# Autoreset.net
KiCad netlist of a schematic drawn in Altium Designer
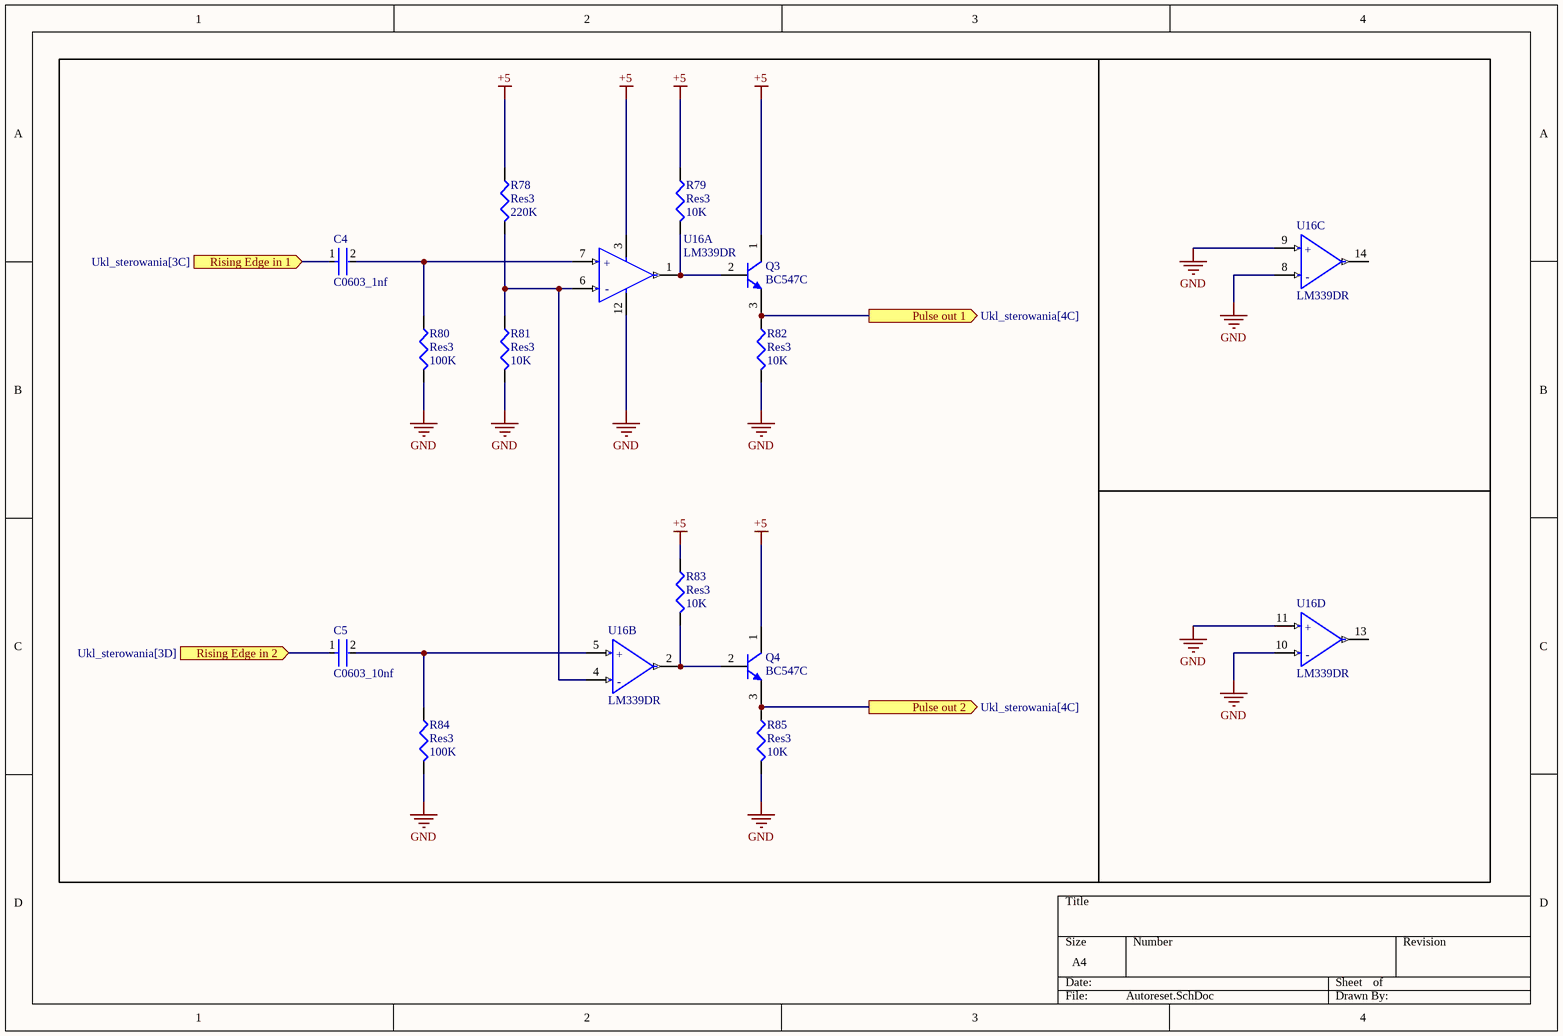
[diagram p0: Autoreset.SchDoc]

(export (version "E")
  (design (tool "Eeschema 10.0.6"))
  (components
    (comp (ref "C4")
      (value "C0603_1nf")
      (footprint "FP-C0603C-CF-MFG")
      (description "CAP CER 30PF 50V 5% NP0 0603")
      (fields
        (field (name "MANUFACTURER PART NUMBER") "C0603C300J5GACTU")
        (field (name "MANUFACTURER") "KEMET")
      )
      (libsource (lib "Altium Content Vault") (part "b4654b650e69147ec39a6b967a45e02"))
    )
    (comp (ref "C5")
      (value "C0603_10nf")
      (footprint "FP-C0603C-CF-MFG")
      (description "CAP CER 30PF 50V 5% NP0 0603")
      (fields
        (field (name "MANUFACTURER PART NUMBER") "C0603C300J5GACTU")
        (field (name "MANUFACTURER") "KEMET")
      )
      (libsource (lib "Altium Content Vault") (part "b4654b650e69147ec39a6b967a45e02"))
    )
    (comp (ref "Q3")
      (value "BC547C")
      (footprint "ONSC-TO-92-3-29-11")
      (description "Amplifier Transistor, NPN Silicon, 3-Pin TO-92, Bulk Box")
      (fields (field (name "MANUFACTURER") "On Semiconductor"))
      (libsource (lib "Altium Content Vault") (part "ONSC-NPN-C1B2E3-3"))
    )
    (comp (ref "Q4")
      (value "BC547C")
      (footprint "ONSC-TO-92-3-29-11")
      (description "Amplifier Transistor, NPN Silicon, 3-Pin TO-92, Bulk Box")
      (fields (field (name "MANUFACTURER") "On Semiconductor"))
      (libsource (lib "Altium Content Vault") (part "ONSC-NPN-C1B2E3-3"))
    )
    (comp (ref "R78")
      (value "Res3")
      (footprint "J1-0603")
      (description "Resistor")
      (fields (field (name "ALTIUM_VALUE") "220K") (field (name "PUBLISHER") "Altium Limited"))
      (libsource (lib "Miscellaneous Devices") (part "Res3"))
    )
    (comp (ref "R79")
      (value "Res3")
      (footprint "J1-0603")
      (description "Resistor")
      (fields (field (name "ALTIUM_VALUE") "10K") (field (name "PUBLISHER") "Altium Limited"))
      (libsource (lib "Miscellaneous Devices") (part "Res3"))
    )
    (comp (ref "R80")
      (value "Res3")
      (footprint "J1-0603")
      (description "Resistor")
      (fields (field (name "ALTIUM_VALUE") "100K") (field (name "PUBLISHER") "Altium Limited"))
      (libsource (lib "Miscellaneous Devices") (part "Res3"))
    )
    (comp (ref "R81")
      (value "Res3")
      (footprint "J1-0603")
      (description "Resistor")
      (fields (field (name "ALTIUM_VALUE") "10K") (field (name "PUBLISHER") "Altium Limited"))
      (libsource (lib "Miscellaneous Devices") (part "Res3"))
    )
    (comp (ref "R82")
      (value "Res3")
      (footprint "J1-0603")
      (description "Resistor")
      (fields (field (name "ALTIUM_VALUE") "10K") (field (name "PUBLISHER") "Altium Limited"))
      (libsource (lib "Miscellaneous Devices") (part "Res3"))
    )
    (comp (ref "R83")
      (value "Res3")
      (footprint "J1-0603")
      (description "Resistor")
      (fields (field (name "ALTIUM_VALUE") "10K") (field (name "PUBLISHER") "Altium Limited"))
      (libsource (lib "Miscellaneous Devices") (part "Res3"))
    )
    (comp (ref "R84")
      (value "Res3")
      (footprint "J1-0603")
      (description "Resistor")
      (fields (field (name "ALTIUM_VALUE") "100K") (field (name "PUBLISHER") "Altium Limited"))
      (libsource (lib "Miscellaneous Devices") (part "Res3"))
    )
    (comp (ref "R85")
      (value "Res3")
      (footprint "J1-0603")
      (description "Resistor")
      (fields (field (name "ALTIUM_VALUE") "10K") (field (name "PUBLISHER") "Altium Limited"))
      (libsource (lib "Miscellaneous Devices") (part "Res3"))
    )
    (comp (ref "U16")
      (value "LM339DR")
      (footprint "FP-D0014A-MFG")
      (description "IC QUAD DIFF COMP 14-SOIC")
      (fields
        (field (name "OCTOPART") "https://octopart.com/lm339dr-texas+instruments-45532")
        (field (name "MANUFACTURER") "Texas Instruments")
      )
      (libsource (lib "Altium Content Vault") (part "e40d3f79f05c88e03941af0c3538ad1"))
    )
  )
  (nets
    (net (code "1") (name "+5") (class "Default")
      (node (ref "Q3") (pin "1") (pinfunction "C_1") (pintype "passive"))
      (node (ref "Q4") (pin "1") (pinfunction "C_1") (pintype "passive"))
      (node (ref "R78") (pin "1") (pinfunction "1_1") (pintype "passive"))
      (node (ref "R79") (pin "1") (pinfunction "1_1") (pintype "passive"))
      (node (ref "R83") (pin "1") (pinfunction "1_1") (pintype "passive"))
      (node (ref "U16") (pin "3") (pinfunction "VCC_3") (pintype "power_in"))
    )
    (net (code "2") (name "/Pulse out 1") (class "Default")
      (node (ref "Q3") (pin "3") (pinfunction "E_3") (pintype "passive"))
      (node (ref "R82") (pin "1") (pinfunction "1_1") (pintype "passive"))
    )
    (net (code "3") (name "/Pulse out 2") (class "Default")
      (node (ref "Q4") (pin "3") (pinfunction "E_3") (pintype "passive"))
      (node (ref "R85") (pin "1") (pinfunction "1_1") (pintype "passive"))
    )
    (net (code "4") (name "/Rising Edge in 1") (class "Default")
      (node (ref "C4") (pin "1") (pinfunction "1_1") (pintype "passive"))
    )
    (net (code "5") (name "/Rising Edge in 2") (class "Default")
      (node (ref "C5") (pin "1") (pinfunction "1_1") (pintype "passive"))
    )
    (net (code "6") (name "GND") (class "Default")
      (node (ref "R80") (pin "2") (pinfunction "2_2") (pintype "passive"))
      (node (ref "R81") (pin "2") (pinfunction "2_2") (pintype "passive"))
      (node (ref "R82") (pin "2") (pinfunction "2_2") (pintype "passive"))
      (node (ref "R84") (pin "2") (pinfunction "2_2") (pintype "passive"))
      (node (ref "R85") (pin "2") (pinfunction "2_2") (pintype "passive"))
      (node (ref "U16") (pin "10") (pinfunction "4IN-_10") (pintype "input"))
      (node (ref "U16") (pin "11") (pinfunction "4IN+_11") (pintype "input"))
      (node (ref "U16") (pin "12") (pinfunction "GND_12") (pintype "power_in"))
      (node (ref "U16") (pin "8") (pinfunction "3IN-_8") (pintype "input"))
      (node (ref "U16") (pin "9") (pinfunction "3IN+_9") (pintype "input"))
    )
    (net (code "7") (name "Net-(Q3-B)") (class "Default")
      (node (ref "Q3") (pin "2") (pinfunction "B_2") (pintype "passive"))
      (node (ref "R79") (pin "2") (pinfunction "2_2") (pintype "passive"))
      (node (ref "U16") (pin "1") (pinfunction "1OUT_1") (pintype "output"))
    )
    (net (code "8") (name "Net-(Q4-B)") (class "Default")
      (node (ref "Q4") (pin "2") (pinfunction "B_2") (pintype "passive"))
      (node (ref "R83") (pin "2") (pinfunction "2_2") (pintype "passive"))
      (node (ref "U16") (pin "2") (pinfunction "2OUT_2") (pintype "output"))
    )
    (net (code "9") (name "Net-(U16A-1IN+)") (class "Default")
      (node (ref "C4") (pin "2") (pinfunction "2_2") (pintype "passive"))
      (node (ref "R80") (pin "1") (pinfunction "1_1") (pintype "passive"))
      (node (ref "U16") (pin "7") (pinfunction "1IN+_7") (pintype "input"))
    )
    (net (code "10") (name "Net-(U16A-1IN-)") (class "Default")
      (node (ref "R78") (pin "2") (pinfunction "2_2") (pintype "passive"))
      (node (ref "R81") (pin "1") (pinfunction "1_1") (pintype "passive"))
      (node (ref "U16") (pin "4") (pinfunction "2IN-_4") (pintype "input"))
      (node (ref "U16") (pin "6") (pinfunction "1IN-_6") (pintype "input"))
    )
    (net (code "11") (name "Net-(U16B-2IN+)") (class "Default")
      (node (ref "C5") (pin "2") (pinfunction "2_2") (pintype "passive"))
      (node (ref "R84") (pin "1") (pinfunction "1_1") (pintype "passive"))
      (node (ref "U16") (pin "5") (pinfunction "2IN+_5") (pintype "input"))
    )
    (net (code "12") (name "unconnected-(U16C-OUT3-Pad14)") (class "Default")
      (node (ref "U16") (pin "14") (pinfunction "OUT3_14") (pintype "output"))
    )
    (net (code "13") (name "unconnected-(U16D-OUT4-Pad13)") (class "Default")
      (node (ref "U16") (pin "13") (pinfunction "OUT4_13") (pintype "output"))
    )
  )
)
